# TheLittleEngineers_org-27C512E-TO-2532S-.net
KiCad netlist of a schematic drawn in EAGLE
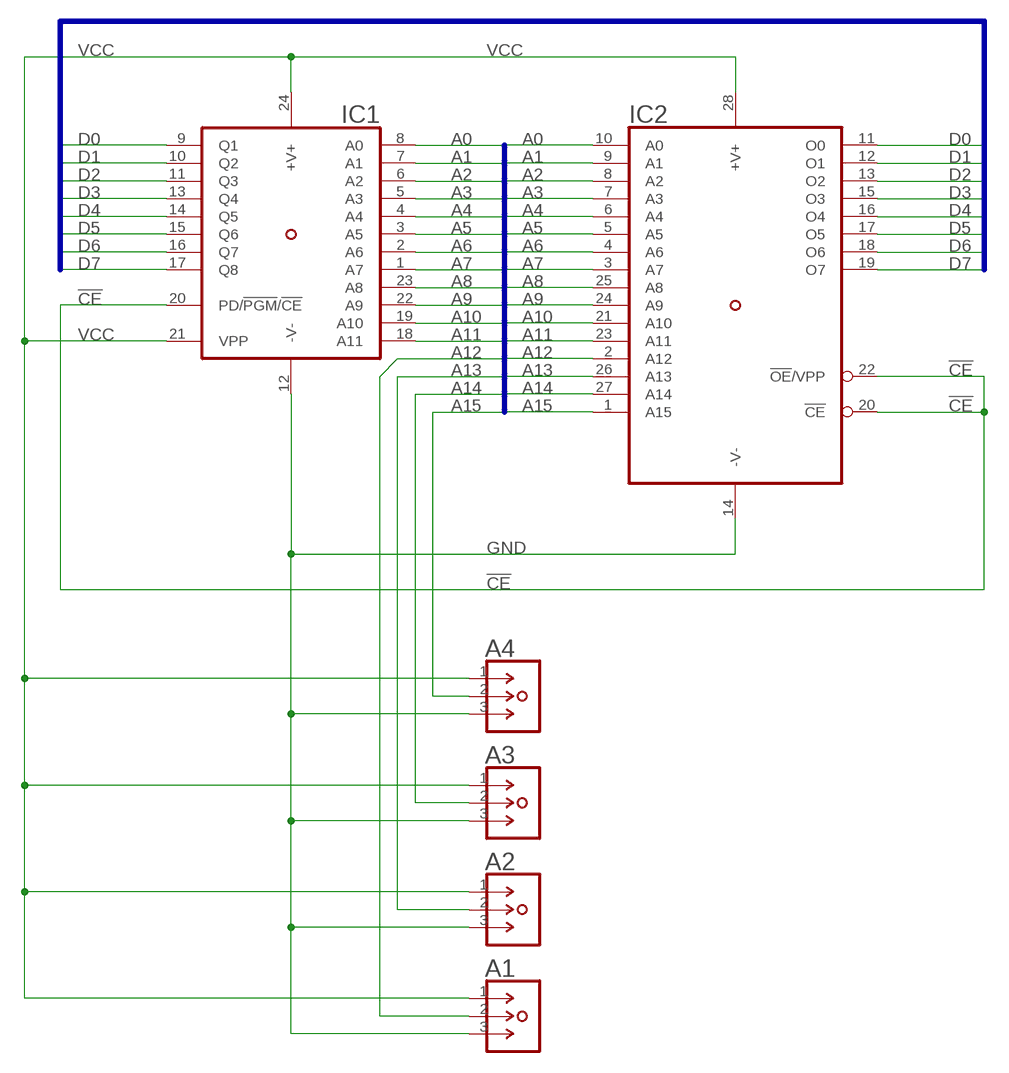
[diagram p0: schematic, sheet 1]

(export (version "E")
  (design (tool "Eeschema 10.0.6"))
  (components
    (comp (ref "A1")
      (value "HEADER-1X03-STAGGERED-S")
      (footprint "eagle-import:HEADER-1X03-STAGGERED")
      (libsource (lib "eagle-import") (part "HEADER-1X03-STAGGERED-S"))
    )
    (comp (ref "A2")
      (value "HEADER-1X03-STAGGERED-S")
      (footprint "eagle-import:HEADER-1X03-STAGGERED")
      (libsource (lib "eagle-import") (part "HEADER-1X03-STAGGERED-S"))
    )
    (comp (ref "A3")
      (value "HEADER-1X03-STAGGERED-S")
      (footprint "eagle-import:HEADER-1X03-STAGGERED")
      (libsource (lib "eagle-import") (part "HEADER-1X03-STAGGERED-S"))
    )
    (comp (ref "A4")
      (value "HEADER-1X03-STAGGERED-S")
      (footprint "eagle-import:HEADER-1X03-STAGGERED")
      (libsource (lib "eagle-import") (part "HEADER-1X03-STAGGERED-S"))
    )
    (comp (ref "IC1")
      (value "2532-NO")
      (footprint "eagle-import:DIL24-6-NO-OUTLINE")
      (libsource (lib "eagle-import") (part "2532-NO"))
    )
    (comp (ref "IC2")
      (value "27C512D-NO")
      (footprint "eagle-import:DIL28-6-NO-OUTLINE")
      (libsource (lib "eagle-import") (part "27C512D-NO"))
    )
  )
  (nets
    (net (code "1") (name "/A0") (class "Default")
      (node (ref "IC1") (pin "8") (pinfunction "A0_8") (pintype "input"))
      (node (ref "IC2") (pin "10") (pinfunction "A0_10") (pintype "input"))
    )
    (net (code "2") (name "/A1") (class "Default")
      (node (ref "IC1") (pin "7") (pinfunction "A1_7") (pintype "input"))
      (node (ref "IC2") (pin "9") (pinfunction "A1_9") (pintype "input"))
    )
    (net (code "3") (name "/A2") (class "Default")
      (node (ref "IC1") (pin "6") (pinfunction "A2_6") (pintype "input"))
      (node (ref "IC2") (pin "8") (pinfunction "A2_8") (pintype "input"))
    )
    (net (code "4") (name "/A3") (class "Default")
      (node (ref "IC1") (pin "5") (pinfunction "A3_5") (pintype "input"))
      (node (ref "IC2") (pin "7") (pinfunction "A3_7") (pintype "input"))
    )
    (net (code "5") (name "/A4") (class "Default")
      (node (ref "IC1") (pin "4") (pinfunction "A4_4") (pintype "input"))
      (node (ref "IC2") (pin "6") (pinfunction "A4_6") (pintype "input"))
    )
    (net (code "6") (name "/A5") (class "Default")
      (node (ref "IC1") (pin "3") (pinfunction "A5_3") (pintype "input"))
      (node (ref "IC2") (pin "5") (pinfunction "A5_5") (pintype "input"))
    )
    (net (code "7") (name "/A6") (class "Default")
      (node (ref "IC1") (pin "2") (pinfunction "A6_2") (pintype "input"))
      (node (ref "IC2") (pin "4") (pinfunction "A6_4") (pintype "input"))
    )
    (net (code "8") (name "/A7") (class "Default")
      (node (ref "IC1") (pin "1") (pinfunction "A7_1") (pintype "input"))
      (node (ref "IC2") (pin "3") (pinfunction "A7_3") (pintype "input"))
    )
    (net (code "9") (name "/A8") (class "Default")
      (node (ref "IC1") (pin "23") (pinfunction "A8_23") (pintype "input"))
      (node (ref "IC2") (pin "25") (pinfunction "A8_25") (pintype "input"))
    )
    (net (code "10") (name "/A9") (class "Default")
      (node (ref "IC1") (pin "22") (pinfunction "A9_22") (pintype "input"))
      (node (ref "IC2") (pin "24") (pinfunction "A9_24") (pintype "input"))
    )
    (net (code "11") (name "/A10") (class "Default")
      (node (ref "IC1") (pin "19") (pinfunction "A10_19") (pintype "input"))
      (node (ref "IC2") (pin "21") (pinfunction "A10_21") (pintype "input"))
    )
    (net (code "12") (name "/A11") (class "Default")
      (node (ref "IC1") (pin "18") (pinfunction "A11_18") (pintype "input"))
      (node (ref "IC2") (pin "23") (pinfunction "A11_23") (pintype "input"))
    )
    (net (code "13") (name "/A12") (class "Default")
      (node (ref "A1") (pin "2") (pinfunction "2_2") (pintype "passive"))
      (node (ref "IC2") (pin "2") (pinfunction "A12_2") (pintype "input"))
    )
    (net (code "14") (name "/A13") (class "Default")
      (node (ref "A2") (pin "2") (pinfunction "2_2") (pintype "passive"))
      (node (ref "IC2") (pin "26") (pinfunction "A13_26") (pintype "input"))
    )
    (net (code "15") (name "/A14") (class "Default")
      (node (ref "A3") (pin "2") (pinfunction "2_2") (pintype "passive"))
      (node (ref "IC2") (pin "27") (pinfunction "A14_27") (pintype "input"))
    )
    (net (code "16") (name "/A15") (class "Default")
      (node (ref "A4") (pin "2") (pinfunction "2_2") (pintype "passive"))
      (node (ref "IC2") (pin "1") (pinfunction "A15_1") (pintype "input"))
    )
    (net (code "17") (name "/D0") (class "Default")
      (node (ref "IC1") (pin "9") (pinfunction "Q1_9") (pintype "tri_state"))
      (node (ref "IC2") (pin "11") (pinfunction "O0_11") (pintype "tri_state"))
    )
    (net (code "18") (name "/D1") (class "Default")
      (node (ref "IC1") (pin "10") (pinfunction "Q2_10") (pintype "tri_state"))
      (node (ref "IC2") (pin "12") (pinfunction "O1_12") (pintype "tri_state"))
    )
    (net (code "19") (name "/D2") (class "Default")
      (node (ref "IC1") (pin "11") (pinfunction "Q3_11") (pintype "tri_state"))
      (node (ref "IC2") (pin "13") (pinfunction "O2_13") (pintype "tri_state"))
    )
    (net (code "20") (name "/D3") (class "Default")
      (node (ref "IC1") (pin "13") (pinfunction "Q4_13") (pintype "tri_state"))
      (node (ref "IC2") (pin "15") (pinfunction "O3_15") (pintype "tri_state"))
    )
    (net (code "21") (name "/D4") (class "Default")
      (node (ref "IC1") (pin "14") (pinfunction "Q5_14") (pintype "tri_state"))
      (node (ref "IC2") (pin "16") (pinfunction "O4_16") (pintype "tri_state"))
    )
    (net (code "22") (name "/D5") (class "Default")
      (node (ref "IC1") (pin "15") (pinfunction "Q6_15") (pintype "tri_state"))
      (node (ref "IC2") (pin "17") (pinfunction "O5_17") (pintype "tri_state"))
    )
    (net (code "23") (name "/D6") (class "Default")
      (node (ref "IC1") (pin "16") (pinfunction "Q7_16") (pintype "tri_state"))
      (node (ref "IC2") (pin "18") (pinfunction "O6_18") (pintype "tri_state"))
    )
    (net (code "24") (name "/D7") (class "Default")
      (node (ref "IC1") (pin "17") (pinfunction "Q8_17") (pintype "tri_state"))
      (node (ref "IC2") (pin "19") (pinfunction "O7_19") (pintype "tri_state"))
    )
    (net (code "25") (name "/GND") (class "Default")
      (node (ref "A1") (pin "3") (pinfunction "3_3") (pintype "passive"))
      (node (ref "A2") (pin "3") (pinfunction "3_3") (pintype "passive"))
      (node (ref "A3") (pin "3") (pinfunction "3_3") (pintype "passive"))
      (node (ref "A4") (pin "3") (pinfunction "3_3") (pintype "passive"))
      (node (ref "IC1") (pin "12") (pinfunction "-V-_12") (pintype "power_in"))
      (node (ref "IC2") (pin "14") (pinfunction "-V-_14") (pintype "power_in"))
    )
    (net (code "26") (name "/VCC") (class "Default")
      (node (ref "A1") (pin "1") (pinfunction "1_1") (pintype "passive"))
      (node (ref "A2") (pin "1") (pinfunction "1_1") (pintype "passive"))
      (node (ref "A3") (pin "1") (pinfunction "1_1") (pintype "passive"))
      (node (ref "A4") (pin "1") (pinfunction "1_1") (pintype "passive"))
      (node (ref "IC1") (pin "21") (pinfunction "VPP_21") (pintype "input"))
      (node (ref "IC1") (pin "24") (pinfunction "+V+_24") (pintype "power_in"))
      (node (ref "IC2") (pin "28") (pinfunction "+V+_28") (pintype "power_in"))
    )
    (net (code "27") (name "/~{CE}") (class "Default")
      (node (ref "IC1") (pin "20") (pinfunction "PD/~{PGM}/~{CE}_20") (pintype "input"))
      (node (ref "IC2") (pin "20") (pinfunction "~{CE}_20") (pintype "input"))
      (node (ref "IC2") (pin "22") (pinfunction "~{OE}/VPP_22") (pintype "input"))
    )
  )
)
